# base_board.net
KiCad netlist of a schematic drawn in EAGLE
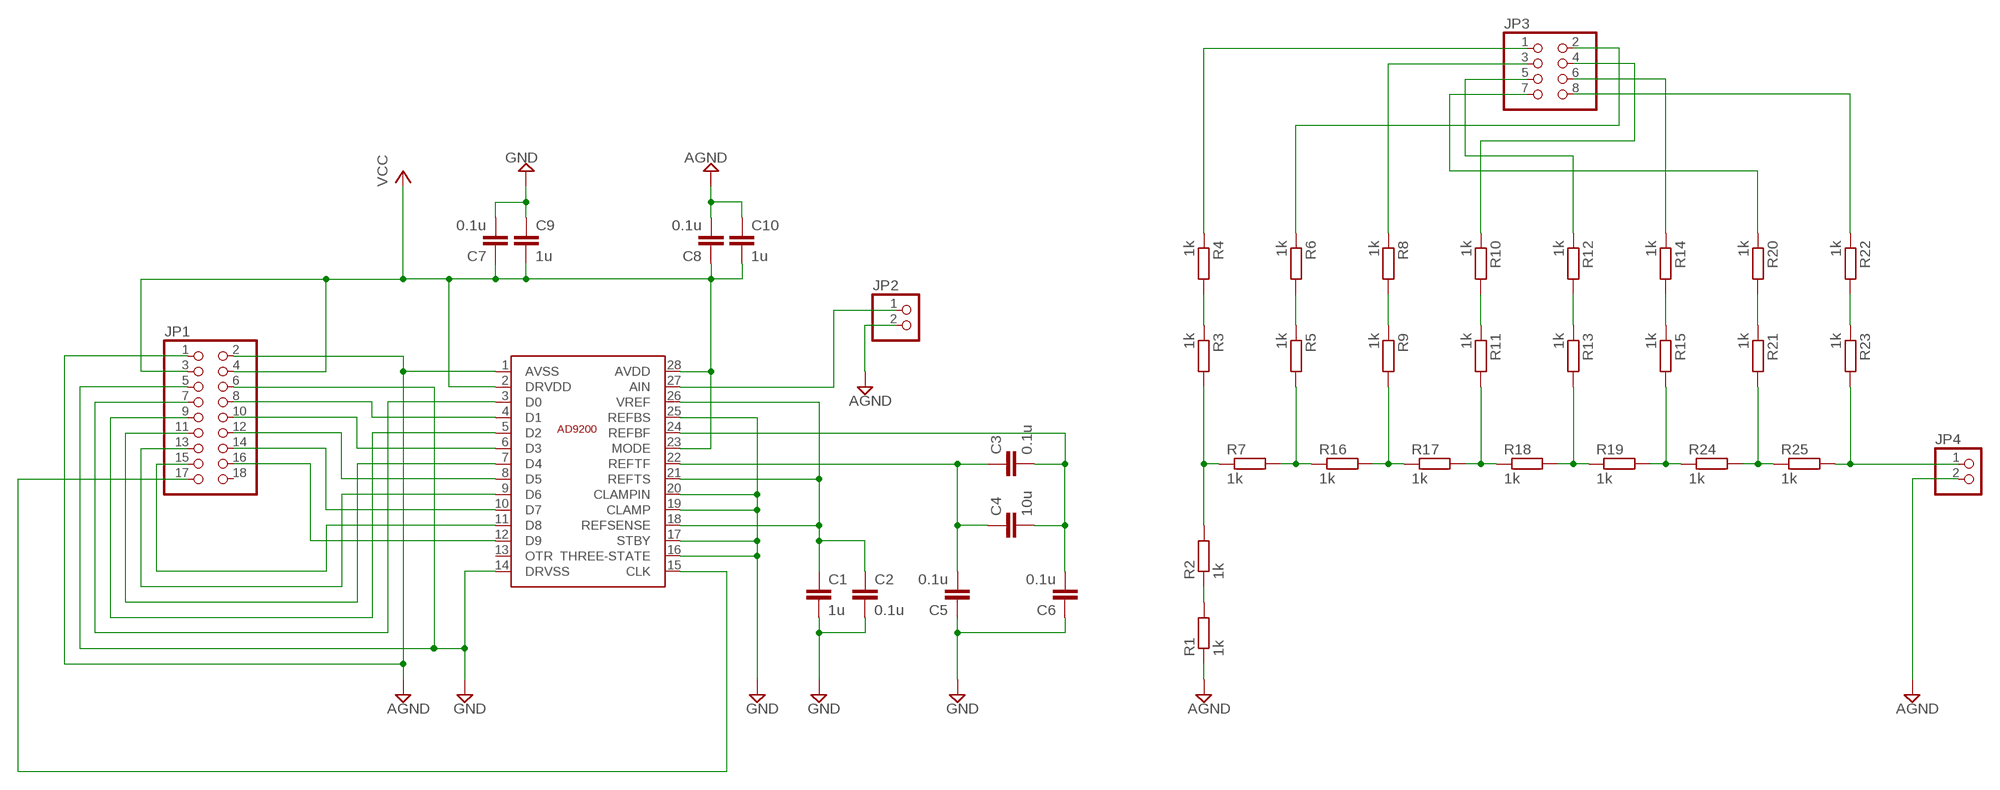
[diagram p0: schematic, sheet 1]

(export (version "E")
  (design (tool "Eeschema 10.0.6"))
  (components
    (comp (ref "C1")
      (value "1u")
      (footprint "eagle-import:C0805")
      (libsource (lib "eagle-import") (part "C-EUC0805"))
    )
    (comp (ref "C2")
      (value "0.1u")
      (footprint "eagle-import:C0805")
      (libsource (lib "eagle-import") (part "C-EUC0805"))
    )
    (comp (ref "C3")
      (value "0.1u")
      (footprint "eagle-import:C0805")
      (libsource (lib "eagle-import") (part "C-EUC0805"))
    )
    (comp (ref "C4")
      (value "10u")
      (footprint "eagle-import:C0805")
      (libsource (lib "eagle-import") (part "C-EUC0805"))
    )
    (comp (ref "C5")
      (value "0.1u")
      (footprint "eagle-import:C0805")
      (libsource (lib "eagle-import") (part "C-EUC0805"))
    )
    (comp (ref "C6")
      (value "0.1u")
      (footprint "eagle-import:C0805")
      (libsource (lib "eagle-import") (part "C-EUC0805"))
    )
    (comp (ref "C7")
      (value "0.1u")
      (footprint "eagle-import:C0805")
      (libsource (lib "eagle-import") (part "C-EUC0805"))
    )
    (comp (ref "C8")
      (value "0.1u")
      (footprint "eagle-import:C0805")
      (libsource (lib "eagle-import") (part "C-EUC0805"))
    )
    (comp (ref "C9")
      (value "1u")
      (footprint "eagle-import:C0805")
      (libsource (lib "eagle-import") (part "C-EUC0805"))
    )
    (comp (ref "C10")
      (value "1u")
      (footprint "eagle-import:C0805")
      (libsource (lib "eagle-import") (part "C-EUC0805"))
    )
    (comp (ref "JP1")
      (value "PINHD-2X9")
      (footprint "eagle-import:2X09")
      (libsource (lib "eagle-import") (part "PINHD-2X9"))
    )
    (comp (ref "JP2")
      (value "PINHD-1X2")
      (footprint "eagle-import:1X02")
      (libsource (lib "eagle-import") (part "PINHD-1X2"))
    )
    (comp (ref "JP3")
      (value "PINHD-2X4")
      (footprint "eagle-import:2X04")
      (libsource (lib "eagle-import") (part "PINHD-2X4"))
    )
    (comp (ref "JP4")
      (value "PINHD-1X2")
      (footprint "eagle-import:1X02")
      (libsource (lib "eagle-import") (part "PINHD-1X2"))
    )
    (comp (ref "R1")
      (value "1k")
      (footprint "eagle-import:R0805")
      (libsource (lib "eagle-import") (part "R-EU_R0805"))
    )
    (comp (ref "R2")
      (value "1k")
      (footprint "eagle-import:R0805")
      (libsource (lib "eagle-import") (part "R-EU_R0805"))
    )
    (comp (ref "R3")
      (value "1k")
      (footprint "eagle-import:R0805")
      (libsource (lib "eagle-import") (part "R-EU_R0805"))
    )
    (comp (ref "R4")
      (value "1k")
      (footprint "eagle-import:R0805")
      (libsource (lib "eagle-import") (part "R-EU_R0805"))
    )
    (comp (ref "R5")
      (value "1k")
      (footprint "eagle-import:R0805")
      (libsource (lib "eagle-import") (part "R-EU_R0805"))
    )
    (comp (ref "R6")
      (value "1k")
      (footprint "eagle-import:R0805")
      (libsource (lib "eagle-import") (part "R-EU_R0805"))
    )
    (comp (ref "R7")
      (value "1k")
      (footprint "eagle-import:R0805")
      (libsource (lib "eagle-import") (part "R-EU_R0805"))
    )
    (comp (ref "R8")
      (value "1k")
      (footprint "eagle-import:R0805")
      (libsource (lib "eagle-import") (part "R-EU_R0805"))
    )
    (comp (ref "R9")
      (value "1k")
      (footprint "eagle-import:R0805")
      (libsource (lib "eagle-import") (part "R-EU_R0805"))
    )
    (comp (ref "R10")
      (value "1k")
      (footprint "eagle-import:R0805")
      (libsource (lib "eagle-import") (part "R-EU_R0805"))
    )
    (comp (ref "R11")
      (value "1k")
      (footprint "eagle-import:R0805")
      (libsource (lib "eagle-import") (part "R-EU_R0805"))
    )
    (comp (ref "R12")
      (value "1k")
      (footprint "eagle-import:R0805")
      (libsource (lib "eagle-import") (part "R-EU_R0805"))
    )
    (comp (ref "R13")
      (value "1k")
      (footprint "eagle-import:R0805")
      (libsource (lib "eagle-import") (part "R-EU_R0805"))
    )
    (comp (ref "R14")
      (value "1k")
      (footprint "eagle-import:R0805")
      (libsource (lib "eagle-import") (part "R-EU_R0805"))
    )
    (comp (ref "R15")
      (value "1k")
      (footprint "eagle-import:R0805")
      (libsource (lib "eagle-import") (part "R-EU_R0805"))
    )
    (comp (ref "R16")
      (value "1k")
      (footprint "eagle-import:R0805")
      (libsource (lib "eagle-import") (part "R-EU_R0805"))
    )
    (comp (ref "R17")
      (value "1k")
      (footprint "eagle-import:R0805")
      (libsource (lib "eagle-import") (part "R-EU_R0805"))
    )
    (comp (ref "R18")
      (value "1k")
      (footprint "eagle-import:R0805")
      (libsource (lib "eagle-import") (part "R-EU_R0805"))
    )
    (comp (ref "R19")
      (value "1k")
      (footprint "eagle-import:R0805")
      (libsource (lib "eagle-import") (part "R-EU_R0805"))
    )
    (comp (ref "R20")
      (value "1k")
      (footprint "eagle-import:R0805")
      (libsource (lib "eagle-import") (part "R-EU_R0805"))
    )
    (comp (ref "R21")
      (value "1k")
      (footprint "eagle-import:R0805")
      (libsource (lib "eagle-import") (part "R-EU_R0805"))
    )
    (comp (ref "R22")
      (value "1k")
      (footprint "eagle-import:R0805")
      (libsource (lib "eagle-import") (part "R-EU_R0805"))
    )
    (comp (ref "R23")
      (value "1k")
      (footprint "eagle-import:R0805")
      (libsource (lib "eagle-import") (part "R-EU_R0805"))
    )
    (comp (ref "R24")
      (value "1k")
      (footprint "eagle-import:R0805")
      (libsource (lib "eagle-import") (part "R-EU_R0805"))
    )
    (comp (ref "R25")
      (value "1k")
      (footprint "eagle-import:R0805")
      (libsource (lib "eagle-import") (part "R-EU_R0805"))
    )
    (comp (ref "U$2")
      (value "AD9200ARZ")
      (footprint "eagle-import:SSOP28")
      (libsource (lib "eagle-import") (part "AD9200ARZ"))
    )
  )
  (nets
    (net (code "1") (name "AGND") (class "Default")
      (node (ref "C10") (pin "1") (pinfunction "1_1") (pintype "passive"))
      (node (ref "C8") (pin "2") (pinfunction "2_2") (pintype "passive"))
      (node (ref "JP1") (pin "1") (pinfunction "1_1") (pintype "passive"))
      (node (ref "JP1") (pin "2") (pinfunction "2_2") (pintype "passive"))
      (node (ref "JP2") (pin "2") (pinfunction "2_2") (pintype "passive"))
      (node (ref "JP4") (pin "2") (pinfunction "2_2") (pintype "passive"))
      (node (ref "R1") (pin "1") (pinfunction "1_1") (pintype "passive"))
      (node (ref "U$2") (pin "1") (pinfunction "AVSS_1") (pintype "bidirectional"))
    )
    (net (code "2") (name "GND") (class "Default")
      (node (ref "C1") (pin "2") (pinfunction "2_2") (pintype "passive"))
      (node (ref "C2") (pin "2") (pinfunction "2_2") (pintype "passive"))
      (node (ref "C5") (pin "1") (pinfunction "1_1") (pintype "passive"))
      (node (ref "C6") (pin "1") (pinfunction "1_1") (pintype "passive"))
      (node (ref "C7") (pin "2") (pinfunction "2_2") (pintype "passive"))
      (node (ref "C9") (pin "1") (pinfunction "1_1") (pintype "passive"))
      (node (ref "JP1") (pin "5") (pinfunction "5_5") (pintype "passive"))
      (node (ref "JP1") (pin "6") (pinfunction "6_6") (pintype "passive"))
      (node (ref "U$2") (pin "14") (pinfunction "DRVSS_14") (pintype "bidirectional"))
      (node (ref "U$2") (pin "16") (pinfunction "THREE-STATE_16") (pintype "bidirectional"))
      (node (ref "U$2") (pin "17") (pinfunction "STBY_17") (pintype "bidirectional"))
      (node (ref "U$2") (pin "19") (pinfunction "CLAMP_19") (pintype "bidirectional"))
      (node (ref "U$2") (pin "20") (pinfunction "CLAMPIN_20") (pintype "bidirectional"))
      (node (ref "U$2") (pin "25") (pinfunction "REFBS_25") (pintype "bidirectional"))
    )
    (net (code "3") (name "Net-(JP3-Pad1)") (class "Default")
      (node (ref "JP3") (pin "1") (pinfunction "1_1") (pintype "passive"))
      (node (ref "R4") (pin "1") (pinfunction "1_1") (pintype "passive"))
    )
    (net (code "4") (name "Net-(JP3-Pad2)") (class "Default")
      (node (ref "JP3") (pin "2") (pinfunction "2_2") (pintype "passive"))
      (node (ref "R6") (pin "1") (pinfunction "1_1") (pintype "passive"))
    )
    (net (code "5") (name "Net-(JP3-Pad3)") (class "Default")
      (node (ref "JP3") (pin "3") (pinfunction "3_3") (pintype "passive"))
      (node (ref "R8") (pin "1") (pinfunction "1_1") (pintype "passive"))
    )
    (net (code "6") (name "Net-(JP3-Pad4)") (class "Default")
      (node (ref "JP3") (pin "4") (pinfunction "4_4") (pintype "passive"))
      (node (ref "R10") (pin "1") (pinfunction "1_1") (pintype "passive"))
    )
    (net (code "7") (name "Net-(JP3-Pad5)") (class "Default")
      (node (ref "JP3") (pin "5") (pinfunction "5_5") (pintype "passive"))
      (node (ref "R12") (pin "1") (pinfunction "1_1") (pintype "passive"))
    )
    (net (code "8") (name "Net-(JP3-Pad6)") (class "Default")
      (node (ref "JP3") (pin "6") (pinfunction "6_6") (pintype "passive"))
      (node (ref "R14") (pin "1") (pinfunction "1_1") (pintype "passive"))
    )
    (net (code "9") (name "Net-(JP3-Pad7)") (class "Default")
      (node (ref "JP3") (pin "7") (pinfunction "7_7") (pintype "passive"))
      (node (ref "R20") (pin "1") (pinfunction "1_1") (pintype "passive"))
    )
    (net (code "10") (name "Net-(JP3-Pad8)") (class "Default")
      (node (ref "JP3") (pin "8") (pinfunction "8_8") (pintype "passive"))
      (node (ref "R22") (pin "1") (pinfunction "1_1") (pintype "passive"))
    )
    (net (code "11") (name "Net-(JP4-Pad1)") (class "Default")
      (node (ref "JP4") (pin "1") (pinfunction "1_1") (pintype "passive"))
      (node (ref "R23") (pin "2") (pinfunction "2_2") (pintype "passive"))
      (node (ref "R25") (pin "2") (pinfunction "2_2") (pintype "passive"))
    )
    (net (code "12") (name "Net-(R1-Pad2)") (class "Default")
      (node (ref "R1") (pin "2") (pinfunction "2_2") (pintype "passive"))
      (node (ref "R2") (pin "1") (pinfunction "1_1") (pintype "passive"))
    )
    (net (code "13") (name "Net-(R2-Pad2)") (class "Default")
      (node (ref "R2") (pin "2") (pinfunction "2_2") (pintype "passive"))
      (node (ref "R3") (pin "2") (pinfunction "2_2") (pintype "passive"))
      (node (ref "R7") (pin "1") (pinfunction "1_1") (pintype "passive"))
    )
    (net (code "14") (name "Net-(R3-Pad1)") (class "Default")
      (node (ref "R3") (pin "1") (pinfunction "1_1") (pintype "passive"))
      (node (ref "R4") (pin "2") (pinfunction "2_2") (pintype "passive"))
    )
    (net (code "15") (name "Net-(R5-Pad1)") (class "Default")
      (node (ref "R5") (pin "1") (pinfunction "1_1") (pintype "passive"))
      (node (ref "R6") (pin "2") (pinfunction "2_2") (pintype "passive"))
    )
    (net (code "16") (name "Net-(R8-Pad2)") (class "Default")
      (node (ref "R8") (pin "2") (pinfunction "2_2") (pintype "passive"))
      (node (ref "R9") (pin "1") (pinfunction "1_1") (pintype "passive"))
    )
    (net (code "17") (name "Net-(R10-Pad2)") (class "Default")
      (node (ref "R10") (pin "2") (pinfunction "2_2") (pintype "passive"))
      (node (ref "R11") (pin "1") (pinfunction "1_1") (pintype "passive"))
    )
    (net (code "18") (name "Net-(R11-Pad2)") (class "Default")
      (node (ref "R11") (pin "2") (pinfunction "2_2") (pintype "passive"))
      (node (ref "R17") (pin "2") (pinfunction "2_2") (pintype "passive"))
      (node (ref "R18") (pin "1") (pinfunction "1_1") (pintype "passive"))
    )
    (net (code "19") (name "Net-(R12-Pad2)") (class "Default")
      (node (ref "R12") (pin "2") (pinfunction "2_2") (pintype "passive"))
      (node (ref "R13") (pin "1") (pinfunction "1_1") (pintype "passive"))
    )
    (net (code "20") (name "Net-(R13-Pad2)") (class "Default")
      (node (ref "R13") (pin "2") (pinfunction "2_2") (pintype "passive"))
      (node (ref "R18") (pin "2") (pinfunction "2_2") (pintype "passive"))
      (node (ref "R19") (pin "1") (pinfunction "1_1") (pintype "passive"))
    )
    (net (code "21") (name "Net-(R14-Pad2)") (class "Default")
      (node (ref "R14") (pin "2") (pinfunction "2_2") (pintype "passive"))
      (node (ref "R15") (pin "1") (pinfunction "1_1") (pintype "passive"))
    )
    (net (code "22") (name "Net-(R15-Pad2)") (class "Default")
      (node (ref "R15") (pin "2") (pinfunction "2_2") (pintype "passive"))
      (node (ref "R19") (pin "2") (pinfunction "2_2") (pintype "passive"))
      (node (ref "R24") (pin "1") (pinfunction "1_1") (pintype "passive"))
    )
    (net (code "23") (name "Net-(R16-Pad1)") (class "Default")
      (node (ref "R16") (pin "1") (pinfunction "1_1") (pintype "passive"))
      (node (ref "R5") (pin "2") (pinfunction "2_2") (pintype "passive"))
      (node (ref "R7") (pin "2") (pinfunction "2_2") (pintype "passive"))
    )
    (net (code "24") (name "Net-(R16-Pad2)") (class "Default")
      (node (ref "R16") (pin "2") (pinfunction "2_2") (pintype "passive"))
      (node (ref "R17") (pin "1") (pinfunction "1_1") (pintype "passive"))
      (node (ref "R9") (pin "2") (pinfunction "2_2") (pintype "passive"))
    )
    (net (code "25") (name "Net-(R20-Pad2)") (class "Default")
      (node (ref "R20") (pin "2") (pinfunction "2_2") (pintype "passive"))
      (node (ref "R21") (pin "1") (pinfunction "1_1") (pintype "passive"))
    )
    (net (code "26") (name "Net-(R21-Pad2)") (class "Default")
      (node (ref "R21") (pin "2") (pinfunction "2_2") (pintype "passive"))
      (node (ref "R24") (pin "2") (pinfunction "2_2") (pintype "passive"))
      (node (ref "R25") (pin "1") (pinfunction "1_1") (pintype "passive"))
    )
    (net (code "27") (name "Net-(R22-Pad2)") (class "Default")
      (node (ref "R22") (pin "2") (pinfunction "2_2") (pintype "passive"))
      (node (ref "R23") (pin "1") (pinfunction "1_1") (pintype "passive"))
    )
    (net (code "28") (name "Net-(U$2-AIN)") (class "Default")
      (node (ref "JP2") (pin "1") (pinfunction "1_1") (pintype "passive"))
      (node (ref "U$2") (pin "27") (pinfunction "AIN_27") (pintype "bidirectional"))
    )
    (net (code "29") (name "Net-(U$2-CLK)") (class "Default")
      (node (ref "JP1") (pin "17") (pinfunction "17_17") (pintype "passive"))
      (node (ref "U$2") (pin "15") (pinfunction "CLK_15") (pintype "bidirectional"))
    )
    (net (code "30") (name "Net-(U$2-D0)") (class "Default")
      (node (ref "JP1") (pin "7") (pinfunction "7_7") (pintype "passive"))
      (node (ref "U$2") (pin "3") (pinfunction "D0_3") (pintype "bidirectional"))
    )
    (net (code "31") (name "Net-(U$2-D1)") (class "Default")
      (node (ref "JP1") (pin "8") (pinfunction "8_8") (pintype "passive"))
      (node (ref "U$2") (pin "4") (pinfunction "D1_4") (pintype "bidirectional"))
    )
    (net (code "32") (name "Net-(U$2-D2)") (class "Default")
      (node (ref "JP1") (pin "9") (pinfunction "9_9") (pintype "passive"))
      (node (ref "U$2") (pin "5") (pinfunction "D2_5") (pintype "bidirectional"))
    )
    (net (code "33") (name "Net-(U$2-D3)") (class "Default")
      (node (ref "JP1") (pin "10") (pinfunction "10_10") (pintype "passive"))
      (node (ref "U$2") (pin "6") (pinfunction "D3_6") (pintype "bidirectional"))
    )
    (net (code "34") (name "Net-(U$2-D4)") (class "Default")
      (node (ref "JP1") (pin "11") (pinfunction "11_11") (pintype "passive"))
      (node (ref "U$2") (pin "7") (pinfunction "D4_7") (pintype "bidirectional"))
    )
    (net (code "35") (name "Net-(U$2-D5)") (class "Default")
      (node (ref "JP1") (pin "12") (pinfunction "12_12") (pintype "passive"))
      (node (ref "U$2") (pin "8") (pinfunction "D5_8") (pintype "bidirectional"))
    )
    (net (code "36") (name "Net-(U$2-D6)") (class "Default")
      (node (ref "JP1") (pin "13") (pinfunction "13_13") (pintype "passive"))
      (node (ref "U$2") (pin "9") (pinfunction "D6_9") (pintype "bidirectional"))
    )
    (net (code "37") (name "Net-(U$2-D7)") (class "Default")
      (node (ref "JP1") (pin "14") (pinfunction "14_14") (pintype "passive"))
      (node (ref "U$2") (pin "10") (pinfunction "D7_10") (pintype "bidirectional"))
    )
    (net (code "38") (name "Net-(U$2-D8)") (class "Default")
      (node (ref "JP1") (pin "15") (pinfunction "15_15") (pintype "passive"))
      (node (ref "U$2") (pin "11") (pinfunction "D8_11") (pintype "bidirectional"))
    )
    (net (code "39") (name "Net-(U$2-D9)") (class "Default")
      (node (ref "JP1") (pin "16") (pinfunction "16_16") (pintype "passive"))
      (node (ref "U$2") (pin "12") (pinfunction "D9_12") (pintype "bidirectional"))
    )
    (net (code "40") (name "Net-(U$2-REFBF)") (class "Default")
      (node (ref "C3") (pin "2") (pinfunction "2_2") (pintype "passive"))
      (node (ref "C4") (pin "2") (pinfunction "2_2") (pintype "passive"))
      (node (ref "C6") (pin "2") (pinfunction "2_2") (pintype "passive"))
      (node (ref "U$2") (pin "24") (pinfunction "REFBF_24") (pintype "bidirectional"))
    )
    (net (code "41") (name "Net-(U$2-REFSENSE)") (class "Default")
      (node (ref "C1") (pin "1") (pinfunction "1_1") (pintype "passive"))
      (node (ref "C2") (pin "1") (pinfunction "1_1") (pintype "passive"))
      (node (ref "U$2") (pin "18") (pinfunction "REFSENSE_18") (pintype "bidirectional"))
      (node (ref "U$2") (pin "21") (pinfunction "REFTS_21") (pintype "bidirectional"))
      (node (ref "U$2") (pin "26") (pinfunction "VREF_26") (pintype "bidirectional"))
    )
    (net (code "42") (name "Net-(U$2-REFTF)") (class "Default")
      (node (ref "C3") (pin "1") (pinfunction "1_1") (pintype "passive"))
      (node (ref "C4") (pin "1") (pinfunction "1_1") (pintype "passive"))
      (node (ref "C5") (pin "2") (pinfunction "2_2") (pintype "passive"))
      (node (ref "U$2") (pin "22") (pinfunction "REFTF_22") (pintype "bidirectional"))
    )
    (net (code "43") (name "VCC") (class "Default")
      (node (ref "C10") (pin "2") (pinfunction "2_2") (pintype "passive"))
      (node (ref "C7") (pin "1") (pinfunction "1_1") (pintype "passive"))
      (node (ref "C8") (pin "1") (pinfunction "1_1") (pintype "passive"))
      (node (ref "C9") (pin "2") (pinfunction "2_2") (pintype "passive"))
      (node (ref "JP1") (pin "3") (pinfunction "3_3") (pintype "passive"))
      (node (ref "JP1") (pin "4") (pinfunction "4_4") (pintype "passive"))
      (node (ref "U$2") (pin "2") (pinfunction "DRVDD_2") (pintype "bidirectional"))
      (node (ref "U$2") (pin "23") (pinfunction "MODE_23") (pintype "bidirectional"))
      (node (ref "U$2") (pin "28") (pinfunction "AVDD_28") (pintype "bidirectional"))
    )
    (net (code "44") (name "unconnected-(JP1-Pad18)") (class "Default")
      (node (ref "JP1") (pin "18") (pinfunction "18_18") (pintype "passive"))
    )
    (net (code "45") (name "unconnected-(U$2-OTR-Pad13)") (class "Default")
      (node (ref "U$2") (pin "13") (pinfunction "OTR_13") (pintype "bidirectional"))
    )
  )
)
